# nm_sys_can_phy.net
KiCad netlist of a schematic drawn in Altium Designer
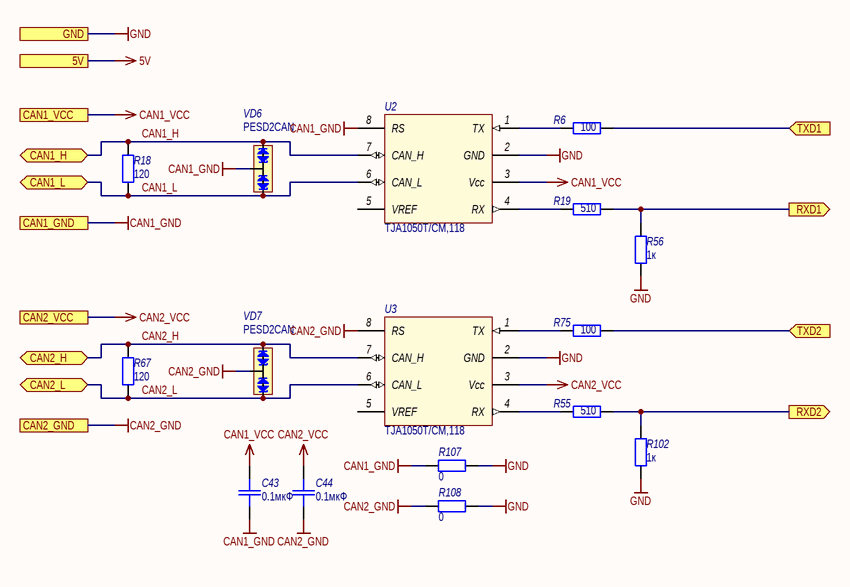
[diagram p0: nm_sys_can_phy.SchDoc]

(export (version "E")
  (design (tool "Eeschema 10.0.6"))
  (components
    (comp (ref "C43")
      (value "0.1мкФ")
      (footprint "SMD_C0603")
      (description "Capacitor")
      (libsource (lib "Passive") (part "Capacitor"))
    )
    (comp (ref "C44")
      (value "0.1мкФ")
      (footprint "SMD_C0603")
      (description "Capacitor")
      (libsource (lib "Passive") (part "Capacitor"))
    )
    (comp (ref "R6")
      (value "100")
      (footprint "SMD_0603")
      (description "Resistor")
      (libsource (lib "") (part "Resistor_2"))
    )
    (comp (ref "R18")
      (value "120")
      (footprint "SMD_0603")
      (description "Resistor")
      (libsource (lib "") (part "Resistor_1"))
    )
    (comp (ref "R19")
      (value "510")
      (footprint "SMD_0603")
      (description "Resistor")
      (libsource (lib "") (part "Resistor_2"))
    )
    (comp (ref "R55")
      (value "510")
      (footprint "SMD_0603")
      (description "Resistor")
      (libsource (lib "") (part "Resistor_2"))
    )
    (comp (ref "R56")
      (value "1к")
      (footprint "SMD_0603")
      (description "Resistor")
      (libsource (lib "") (part "Resistor_1"))
    )
    (comp (ref "R67")
      (value "120")
      (footprint "SMD_0603")
      (description "Resistor")
      (libsource (lib "") (part "Resistor_1"))
    )
    (comp (ref "R75")
      (value "100")
      (footprint "SMD_0603")
      (description "Resistor")
      (libsource (lib "") (part "Resistor_2"))
    )
    (comp (ref "R102")
      (value "1к")
      (footprint "SMD_0603")
      (description "Resistor")
      (libsource (lib "") (part "Resistor_1"))
    )
    (comp (ref "R107")
      (value "0")
      (footprint "SMD_0603")
      (description "Resistor")
      (libsource (lib "Passive") (part "Resistor"))
    )
    (comp (ref "R108")
      (value "0")
      (footprint "SMD_0603")
      (description "Resistor")
      (libsource (lib "Passive") (part "Resistor"))
    )
    (comp (ref "U2")
      (value "TJA1050")
      (footprint "SOIC-8")
      (description "Isolated CAN Transceiver")
      (fields (field (name "НАИМЕНОВАНИЕ") "TJA1050T/CM,118"))
      (libsource (lib "Transceiver") (part "TJA1050"))
    )
    (comp (ref "U3")
      (value "TJA1050")
      (footprint "SOIC-8")
      (description "Isolated CAN Transceiver")
      (fields (field (name "НАИМЕНОВАНИЕ") "TJA1050T/CM,118"))
      (libsource (lib "Transceiver") (part "TJA1050"))
    )
    (comp (ref "VD6")
      (value "PESD2CAN")
      (footprint "SOT-23")
      (description "CAN bus ESD protection diode")
      (fields (field (name "НАИМЕНОВАНИЕ") "PESD2CAN"))
      (libsource (lib "Diod") (part "PESD2CAN"))
    )
    (comp (ref "VD7")
      (value "PESD2CAN")
      (footprint "SOT-23")
      (description "CAN bus ESD protection diode")
      (fields (field (name "НАИМЕНОВАНИЕ") "PESD2CAN"))
      (libsource (lib "Diod") (part "PESD2CAN"))
    )
  )
  (nets
    (net (code "1") (name "/CAN1_H") (class "Default")
      (node (ref "R18") (pin "2") (pinfunction "2_2") (pintype "passive"))
      (node (ref "U2") (pin "7") (pinfunction "CAN_H_7") (pintype "bidirectional"))
      (node (ref "VD6") (pin "2") (pinfunction "C2_2") (pintype "passive"))
    )
    (net (code "2") (name "/CAN1_L") (class "Default")
      (node (ref "R18") (pin "1") (pinfunction "1_1") (pintype "passive"))
      (node (ref "U2") (pin "6") (pinfunction "CAN_L_6") (pintype "bidirectional"))
      (node (ref "VD6") (pin "1") (pinfunction "C1_1") (pintype "passive"))
    )
    (net (code "3") (name "/CAN2_H") (class "Default")
      (node (ref "R67") (pin "2") (pinfunction "2_2") (pintype "passive"))
      (node (ref "U3") (pin "7") (pinfunction "CAN_H_7") (pintype "bidirectional"))
      (node (ref "VD7") (pin "2") (pinfunction "C2_2") (pintype "passive"))
    )
    (net (code "4") (name "/CAN2_L") (class "Default")
      (node (ref "R67") (pin "1") (pinfunction "1_1") (pintype "passive"))
      (node (ref "U3") (pin "6") (pinfunction "CAN_L_6") (pintype "bidirectional"))
      (node (ref "VD7") (pin "1") (pinfunction "C1_1") (pintype "passive"))
    )
    (net (code "5") (name "/RXD1") (class "Default")
      (node (ref "R19") (pin "2") (pinfunction "2_2") (pintype "passive"))
      (node (ref "R56") (pin "2") (pinfunction "2_2") (pintype "passive"))
    )
    (net (code "6") (name "/RXD2") (class "Default")
      (node (ref "R102") (pin "2") (pinfunction "2_2") (pintype "passive"))
      (node (ref "R55") (pin "2") (pinfunction "2_2") (pintype "passive"))
    )
    (net (code "7") (name "/TXD1") (class "Default")
      (node (ref "R6") (pin "2") (pinfunction "2_2") (pintype "passive"))
    )
    (net (code "8") (name "/TXD2") (class "Default")
      (node (ref "R75") (pin "2") (pinfunction "2_2") (pintype "passive"))
    )
    (net (code "10") (name "CAN1_GND") (class "Default")
      (node (ref "C43") (pin "1") (pinfunction "1_1") (pintype "passive"))
      (node (ref "R107") (pin "2") (pinfunction "2_2") (pintype "passive"))
      (node (ref "U2") (pin "8") (pinfunction "RS_8") (pintype "power_in"))
      (node (ref "VD6") (pin "3") (pinfunction "CC_3") (pintype "passive"))
    )
    (net (code "11") (name "CAN1_VCC") (class "Default")
      (node (ref "C43") (pin "2") (pinfunction "2_2") (pintype "passive"))
      (node (ref "U2") (pin "3") (pinfunction "Vcc_3") (pintype "power_in"))
    )
    (net (code "12") (name "CAN2_GND") (class "Default")
      (node (ref "C44") (pin "1") (pinfunction "1_1") (pintype "passive"))
      (node (ref "R108") (pin "2") (pinfunction "2_2") (pintype "passive"))
      (node (ref "U3") (pin "8") (pinfunction "RS_8") (pintype "power_in"))
      (node (ref "VD7") (pin "3") (pinfunction "CC_3") (pintype "passive"))
    )
    (net (code "13") (name "CAN2_VCC") (class "Default")
      (node (ref "C44") (pin "2") (pinfunction "2_2") (pintype "passive"))
      (node (ref "U3") (pin "3") (pinfunction "Vcc_3") (pintype "power_in"))
    )
    (net (code "14") (name "GND") (class "Default")
      (node (ref "R102") (pin "1") (pinfunction "1_1") (pintype "passive"))
      (node (ref "R107") (pin "1") (pinfunction "1_1") (pintype "passive"))
      (node (ref "R108") (pin "1") (pinfunction "1_1") (pintype "passive"))
      (node (ref "R56") (pin "1") (pinfunction "1_1") (pintype "passive"))
      (node (ref "U2") (pin "2") (pinfunction "GND_2") (pintype "power_in"))
      (node (ref "U3") (pin "2") (pinfunction "GND_2") (pintype "power_in"))
    )
    (net (code "15") (name "Net-(U2-RX)") (class "Default")
      (node (ref "R19") (pin "1") (pinfunction "1_1") (pintype "passive"))
      (node (ref "U2") (pin "4") (pinfunction "RX_4") (pintype "output"))
    )
    (net (code "16") (name "Net-(U2-TX)") (class "Default")
      (node (ref "R6") (pin "1") (pinfunction "1_1") (pintype "passive"))
      (node (ref "U2") (pin "1") (pinfunction "TX_1") (pintype "input"))
    )
    (net (code "17") (name "Net-(U3-RX)") (class "Default")
      (node (ref "R55") (pin "1") (pinfunction "1_1") (pintype "passive"))
      (node (ref "U3") (pin "4") (pinfunction "RX_4") (pintype "output"))
    )
    (net (code "18") (name "Net-(U3-TX)") (class "Default")
      (node (ref "R75") (pin "1") (pinfunction "1_1") (pintype "passive"))
      (node (ref "U3") (pin "1") (pinfunction "TX_1") (pintype "input"))
    )
    (net (code "19") (name "unconnected-(U2-VREF-Pad5)") (class "Default")
      (node (ref "U2") (pin "5") (pinfunction "VREF_5") (pintype "power_in"))
    )
    (net (code "20") (name "unconnected-(U3-VREF-Pad5)") (class "Default")
      (node (ref "U3") (pin "5") (pinfunction "VREF_5") (pintype "power_in"))
    )
  )
)
